# EasyEDApro.net
KiCad netlist of a schematic drawn in EasyEDA Pro
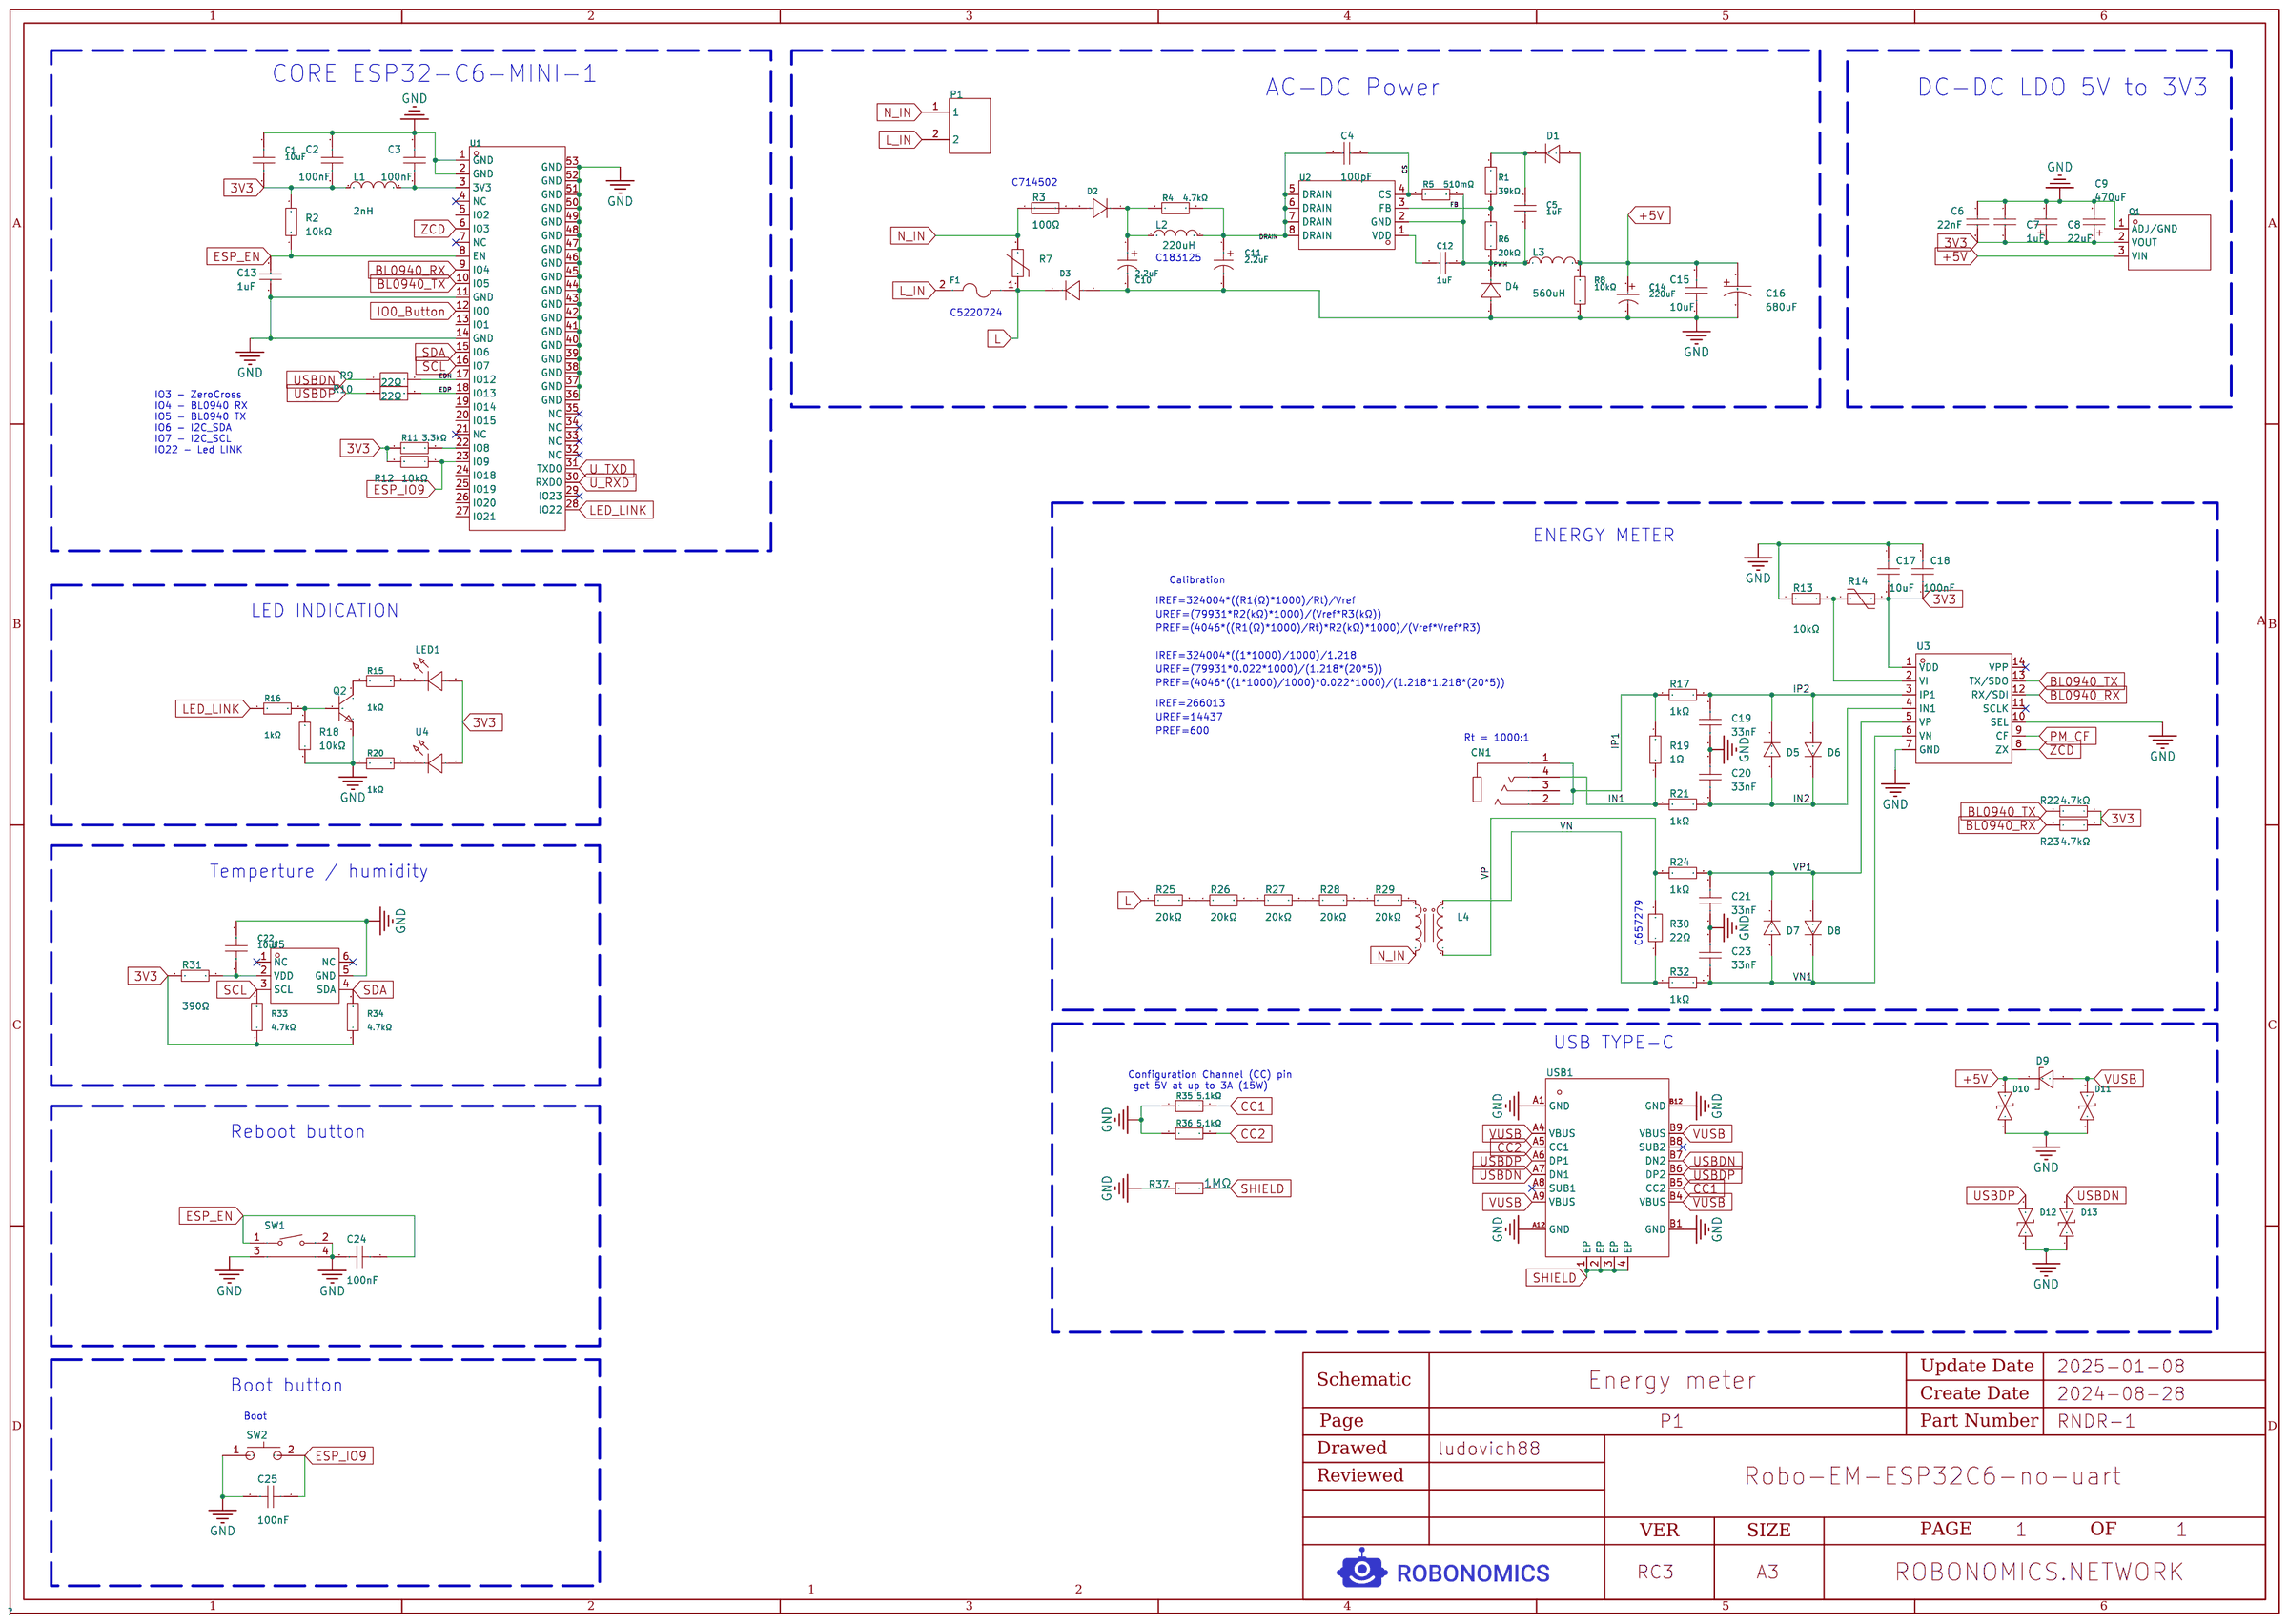
[diagram p0: schematic sheet]

(export (version "E")
  (design (tool "Eeschema 10.0.6"))
  (components
    (comp (ref "C1")
      (value "10uF")
      (footprint "easyedapro:C0603")
      (fields
        (field (name "Manufacturer Part") "GRM188R61E106KA73D")
        (field (name "Manufacturer") "muRata(村田)")
      )
      (libsource (lib "easyedapro") (part "GRM188R61E106KA73D"))
    )
    (comp (ref "C2")
      (value "100nF")
      (fields
        (field (name "Manufacturer Part") "CC0603KRX7R9BB104")
        (field (name "Manufacturer") "YAGEO(国巨)")
      )
      (libsource (lib "easyedapro") (part "0603f104z500"))
    )
    (comp (ref "C3")
      (value "100nF")
      (fields
        (field (name "Manufacturer Part") "CC0603KRX7R9BB104")
        (field (name "Manufacturer") "YAGEO(国巨)")
      )
      (libsource (lib "easyedapro") (part "0603f104z500"))
    )
    (comp (ref "C4")
      (value "100pF")
      (footprint "easyedapro:C1206")
      (fields (field (name "Manufacturer Part") "1206CG101J102NT") (field (name "Manufacturer") "FH(风华)"))
      (libsource (lib "easyedapro") (part "1206CG101J102NT"))
    )
    (comp (ref "C5")
      (value "1uF")
      (footprint "easyedapro:C0805")
      (fields
        (field (name "Manufacturer Part") "CL21B105KBFNNNE")
        (field (name "Manufacturer") "SAMSUNG(三星)")
      )
      (libsource (lib "easyedapro") (part "CL21B105KBFNNNE"))
    )
    (comp (ref "C6")
      (value "22nF")
      (footprint "easyedapro:C0603")
      (description "Capacitance:22nF Tolerance:±10% Tolerance:±10% Voltage Rated:50V Temperature Coefficient:X7R")
      (fields
        (field (name "Manufacturer Part") "CL10B223KB8NNNC")
        (field (name "Manufacturer") "SAMSUNG(三星)")
      )
      (libsource (lib "easyedapro") (part "CL10B223KB8NNNC"))
    )
    (comp (ref "C7")
      (value "1uF")
      (footprint "easyedapro:C0603")
      (description "Capacitance:1uF Tolerance:±10% Tolerance:±10% Voltage Rated:50V Temperature Coefficient:X5R")
      (fields
        (field (name "Manufacturer Part") "CL10A105KB8NNNC")
        (field (name "Manufacturer") "SAMSUNG(三星)")
      )
      (libsource (lib "easyedapro") (part "CL10A105KB8NNNC"))
    )
    (comp (ref "C8")
      (value "22uF")
      (footprint "easyedapro:CASE-A_3216")
      (fields (field (name "Manufacturer Part") "TAJA226K010RNJ") (field (name "Manufacturer") "Kyocera AVX"))
      (libsource (lib "easyedapro") (part "TAJA226K010RNJ"))
    )
    (comp (ref "C9")
      (value "470uF")
      (footprint "easyedapro:CASE-D_7343")
      (fields (field (name "Manufacturer Part") "6TPE470MAZU") (field (name "Manufacturer") "PANASONIC(松下)"))
      (libsource (lib "easyedapro") (part "6TPE470MAZU"))
    )
    (comp (ref "C10")
      (value "2.2uF")
      (footprint "easyedapro:CAP-TH_BD6.3-P2.50-D0.5-FD")
      (fields
        (field (name "Manufacturer Part") "ECH2GM2R2E09OTZO")
        (field (name "Manufacturer") "Yunxing(云星)")
      )
      (libsource (lib "easyedapro") (part "ECH2GM2R2E09OTZO"))
    )
    (comp (ref "C11")
      (value "2.2uF")
      (footprint "easyedapro:CAP-TH_BD6.3-P2.50-D0.5-FD")
      (fields
        (field (name "Manufacturer Part") "ECH2GM2R2E09OTZO")
        (field (name "Manufacturer") "Yunxing(云星)")
      )
      (libsource (lib "easyedapro") (part "ECH2GM2R2E09OTZO"))
    )
    (comp (ref "C12")
      (value "1uF")
      (footprint "easyedapro:C0805")
      (fields
        (field (name "Manufacturer Part") "CL21B105KBFNNNE")
        (field (name "Manufacturer") "SAMSUNG(三星)")
      )
      (libsource (lib "easyedapro") (part "CL21B105KBFNNNE"))
    )
    (comp (ref "C13")
      (value "1uF")
      (footprint "easyedapro:C0603")
      (fields
        (field (name "Manufacturer Part") "CL10A105KO8NNNC")
        (field (name "Manufacturer") "SAMSUNG(三星)")
      )
      (libsource (lib "easyedapro") (part "CL10A105KO8NNNC"))
    )
    (comp (ref "C14")
      (value "220uF")
      (footprint "easyedapro:CAP-TH_BD6.3-P2.50-D1.0-FD")
      (fields
        (field (name "Manufacturer Part") "16YXJ220M6.3X11")
        (field (name "Manufacturer") "rubycon(红宝石)")
      )
      (libsource (lib "easyedapro") (part "16YXJ220M6.3X11"))
    )
    (comp (ref "C15")
      (value "10uF")
      (fields
        (field (name "Manufacturer Part") "CL10A106KP8NNNC")
        (field (name "Manufacturer") "SAMSUNG(三星)")
      )
      (libsource (lib "easyedapro") (part "cl10a106kp8nnnc"))
    )
    (comp (ref "C16")
      (value "680uF")
      (footprint "easyedapro:CAP-SMD_L7.3-W4.3")
      (fields (field (name "Manufacturer Part") "TAJE687K006RNJ") (field (name "Manufacturer") "KyoceraAVX"))
      (libsource (lib "easyedapro") (part "TAJE687K006RNJ"))
    )
    (comp (ref "C17")
      (value "10uF")
      (footprint "easyedapro:C0603")
      (fields
        (field (name "Manufacturer Part") "CL10A106MQ8NNNC")
        (field (name "Manufacturer") "SAMSUNG(三星)")
      )
      (libsource (lib "easyedapro") (part "CL10A106MQ8NNNC"))
    )
    (comp (ref "C18")
      (value "100nF")
      (footprint "easyedapro:C0603")
      (fields (field (name "Manufacturer Part") "0603ZC104KAT2A") (field (name "Manufacturer") "KyoceraAVX"))
      (libsource (lib "easyedapro") (part "0603ZC104KAT2A"))
    )
    (comp (ref "C19")
      (value "33nF")
      (footprint "easyedapro:C0603")
      (fields
        (field (name "Manufacturer Part") "CC0603JRX7R9BB333")
        (field (name "Manufacturer") "YAGEO(国巨)")
      )
      (libsource (lib "easyedapro") (part "CC0603JRX7R9BB333"))
    )
    (comp (ref "C20")
      (value "33nF")
      (footprint "easyedapro:C0603")
      (fields
        (field (name "Manufacturer Part") "CC0603JRX7R9BB333")
        (field (name "Manufacturer") "YAGEO(国巨)")
      )
      (libsource (lib "easyedapro") (part "CC0603JRX7R9BB333"))
    )
    (comp (ref "C21")
      (value "33nF")
      (footprint "easyedapro:C0603")
      (fields
        (field (name "Manufacturer Part") "CC0603JRX7R9BB333")
        (field (name "Manufacturer") "YAGEO(国巨)")
      )
      (libsource (lib "easyedapro") (part "CC0603JRX7R9BB333"))
    )
    (comp (ref "C22")
      (value "10uF")
      (footprint "easyedapro:C0603")
      (fields
        (field (name "Manufacturer Part") "GRM188R61E106KA73D")
        (field (name "Manufacturer") "muRata(村田)")
      )
      (libsource (lib "easyedapro") (part "GRM188R61E106KA73D"))
    )
    (comp (ref "C23")
      (value "33nF")
      (footprint "easyedapro:C0603")
      (fields
        (field (name "Manufacturer Part") "CC0603JRX7R9BB333")
        (field (name "Manufacturer") "YAGEO(国巨)")
      )
      (libsource (lib "easyedapro") (part "CC0603JRX7R9BB333"))
    )
    (comp (ref "C24")
      (value "100nF")
      (footprint "easyedapro:C0603")
      (fields (field (name "Manufacturer Part") "0603ZC104KAT2A") (field (name "Manufacturer") "KyoceraAVX"))
      (libsource (lib "easyedapro") (part "0603ZC104KAT2A"))
    )
    (comp (ref "C25")
      (value "100nF")
      (footprint "easyedapro:C0603")
      (fields
        (field (name "Manufacturer Part") "CC0603KRX7R9BB104")
        (field (name "Manufacturer") "YAGEO(国巨)")
      )
      (libsource (lib "easyedapro") (part "0603ZC104KAT2A"))
    )
    (comp (ref "CN1")
      (value "PJ-320D")
      (footprint "easyedapro:AUDIO-SMD_PJ-320D")
      (fields (field (name "Manufacturer") "SHOU HAN(首韩)"))
      (libsource (lib "easyedapro") (part "PJ-320D"))
    )
    (comp (ref "D1")
      (value "FR107W")
      (footprint "easyedapro:SOD-123F_L2.8-W1.8-LS3.7-RD")
      (fields (field (name "Manufacturer") "SHIKUES(时科)"))
      (libsource (lib "easyedapro") (part "FR107W_C122857"))
    )
    (comp (ref "D2")
      (value "1N4007")
      (footprint "easyedapro:SOD-123FL_L2.8-W1.8-LS3.7-RD")
      (fields (field (name "Manufacturer") "YONGYUTAI(永裕泰)"))
      (libsource (lib "easyedapro") (part "1N4007_C2892681"))
    )
    (comp (ref "D3")
      (value "1N4007")
      (footprint "easyedapro:SOD-123FL_L2.8-W1.8-LS3.7-RD")
      (fields (field (name "Manufacturer") "YONGYUTAI(永裕泰)"))
      (libsource (lib "easyedapro") (part "1N4007_C2892681"))
    )
    (comp (ref "D4")
      (value "E1J")
      (footprint "easyedapro:SOD-123FL_L2.7-W1.8-LS3.7-RD")
      (fields (field (name "Manufacturer") "LGE(鲁光)"))
      (libsource (lib "easyedapro") (part "E1J_C2940141"))
    )
    (comp (ref "D5")
      (value "1N4148WS")
      (footprint "easyedapro:SOD-323_L1.8-W1.3-LS2.5-RD")
      (fields (field (name "Manufacturer") "CJ(江苏长电/长晶)"))
      (libsource (lib "easyedapro") (part "1N4148WS T4"))
    )
    (comp (ref "D6")
      (value "1N4148WS")
      (footprint "easyedapro:SOD-323_L1.8-W1.3-LS2.5-RD")
      (fields (field (name "Manufacturer") "CJ(江苏长电/长晶)"))
      (libsource (lib "easyedapro") (part "1N4148WS T4"))
    )
    (comp (ref "D7")
      (value "1N4148WS")
      (footprint "easyedapro:SOD-323_L1.8-W1.3-LS2.5-RD")
      (fields (field (name "Manufacturer") "CJ(江苏长电/长晶)"))
      (libsource (lib "easyedapro") (part "1N4148WS T4"))
    )
    (comp (ref "D8")
      (value "1N4148WS")
      (footprint "easyedapro:SOD-323_L1.8-W1.3-LS2.5-RD")
      (fields (field (name "Manufacturer") "CJ(江苏长电/长晶)"))
      (libsource (lib "easyedapro") (part "1N4148WS T4"))
    )
    (comp (ref "D9")
      (value "~")
      (footprint "easyedapro:SOD-323_L1.8-W1.3-LS2.5-RD")
      (description "Reverse Voltage (Vr):40V Average Rectified Current (Io):1A Forward Voltage (Vf@If):600mV@1A")
      (fields (field (name "Manufacturer Part") "1N5819WS") (field (name "Manufacturer") "Hottech(合科泰)"))
      (libsource (lib "easyedapro") (part "1N5819WS"))
    )
    (comp (ref "D10")
      (value "LESD5D5.0CT1G-ES")
      (footprint "easyedapro:SOD-523_L1.2-W0.8-LS1.6-BI")
      (fields
        (field (name "Manufacturer Part") "LESD5D5.0CT1G")
        (field (name "Manufacturer") "ElecSuper(静芯微)")
      )
      (libsource (lib "easyedapro") (part "LESD5D5.0CT1G"))
    )
    (comp (ref "D11")
      (value "LESD5D5.0CT1G-ES")
      (footprint "easyedapro:SOD-523_L1.2-W0.8-LS1.6-BI")
      (fields
        (field (name "Manufacturer Part") "LESD5D5.0CT1G")
        (field (name "Manufacturer") "ElecSuper(静芯微)")
      )
      (libsource (lib "easyedapro") (part "LESD5D5.0CT1G"))
    )
    (comp (ref "D12")
      (value "LESD5D5.0CT1G-ES")
      (footprint "easyedapro:SOD-523_L1.2-W0.8-LS1.6-BI")
      (fields
        (field (name "Manufacturer Part") "LESD5D5.0CT1G")
        (field (name "Manufacturer") "ElecSuper(静芯微)")
      )
      (libsource (lib "easyedapro") (part "LESD5D5.0CT1G"))
    )
    (comp (ref "D13")
      (value "LESD5D5.0CT1G-ES")
      (footprint "easyedapro:SOD-523_L1.2-W0.8-LS1.6-BI")
      (fields
        (field (name "Manufacturer Part") "LESD5D5.0CT1G")
        (field (name "Manufacturer") "ElecSuper(静芯微)")
      )
      (libsource (lib "easyedapro") (part "LESD5D5.0CT1G"))
    )
    (comp (ref "F1")
      (value "JFC2410-1200FS")
      (footprint "easyedapro:F2410")
      (fields (field (name "Manufacturer") "JDTfuse(集电通)"))
      (libsource (lib "easyedapro") (part "JFC2410-1200FS"))
    )
    (comp (ref "L1")
      (value "2nH")
      (footprint "easyedapro:L0603")
      (fields
        (field (name "Manufacturer Part") "SDCL1608C2N0STDF")
        (field (name "Manufacturer") "Sunlord(顺络)")
      )
      (libsource (lib "easyedapro") (part "SDCL1608C2N0STDF_C370234"))
    )
    (comp (ref "L2")
      (value "220uH")
      (footprint "easyedapro:IND-TH_BD4.0-P5.00-D0.8")
      (fields (field (name "Manufacturer Part") "LGA0410-221KP13E") (field (name "Manufacturer") "FH(风华)"))
      (libsource (lib "easyedapro") (part "LGA0410-221KP13E"))
    )
    (comp (ref "L3")
      (value "560uH")
      (footprint "easyedapro:IND-SMD_L10.5-W10.5")
      (description "Inductance: Tolerance:±20% Tolerance:±20% Rated Current: DC Resistance (DCR): Type:屏蔽电感")
      (fields
        (field (name "Manufacturer Part") "SCDS105R-561M-N")
        (field (name "Manufacturer") "chilisin(奇力新)")
      )
      (libsource (lib "easyedapro") (part "SCDS105R-561M-N"))
    )
    (comp (ref "L4")
      (value "HPT225A-G")
      (footprint "easyedapro:XFMR-TH_4P-L19.0-10.0-P7.20")
      (fields (field (name "Manufacturer") "HOP(北京霍远)"))
      (libsource (lib "easyedapro") (part "HPT225A-G"))
    )
    (comp (ref "LED1")
      (value "XL-4008UGC")
      (footprint "easyedapro:LED-SMD_L4.0-W1.4-RD_GREEN")
      (fields (field (name "Manufacturer") "XINGLIGHT(成兴光)"))
      (libsource (lib "easyedapro") (part "XL-4008UGC"))
    )
    (comp (ref "P1")
      (value "WJ128V-5.0-2P")
      (footprint "easyedapro:CONN-TH_2P-P5.00_WJ128V-5.0-2P")
      (fields (field (name "Manufacturer") "KANGNEX(康奈克斯电气)"))
      (libsource (lib "easyedapro") (part "WJ128V-5.0-2P"))
    )
    (comp (ref "Q1")
      (value "AMS1117-3.3V")
      (footprint "easyedapro:SOT-89-3_L4.5-W2.5-P1.50-LS4.2-BR")
      (fields (field (name "Manufacturer") "MSKSEMI(美森科)"))
      (libsource (lib "easyedapro") (part "AMS1117-3.3V_C5120796"))
    )
    (comp (ref "Q2")
      (value "SS8050")
      (footprint "easyedapro:SOT-23-3_L2.9-W1.6-P1.90-LS2.8-BR")
      (fields (field (name "Manufacturer") "Hottech(合科泰)"))
      (libsource (lib "easyedapro") (part "SS8050_C181160"))
    )
    (comp (ref "R1")
      (value "39kΩ")
      (footprint "easyedapro:R0805")
      (fields
        (field (name "Manufacturer Part") "0805W8J0393T5E")
        (field (name "Manufacturer") "UNI-ROYAL(厚声)")
      )
      (libsource (lib "easyedapro") (part "HPCR0805F39K0K9"))
    )
    (comp (ref "R2")
      (value "10kΩ")
      (footprint "easyedapro:R0402")
      (fields (field (name "Manufacturer Part") "RC0402FR-0710KL") (field (name "Manufacturer") "YAGEO(国巨)"))
      (libsource (lib "easyedapro") (part "RC0402FR-0710KL"))
    )
    (comp (ref "R3")
      (value "100Ω")
      (footprint "easyedapro:RES-TH_BD3.5-L9.5-P13.50-D0.6")
      (fields (field (name "Manufacturer Part") "RFS01J1000A520NH") (field (name "Manufacturer") "双羽"))
      (libsource (lib "easyedapro") (part "RFS01J1000A520NH"))
    )
    (comp (ref "R4")
      (value "4.7kΩ")
      (footprint "easyedapro:R0603")
      (fields
        (field (name "Manufacturer Part") "0603WAF4701T5E")
        (field (name "Manufacturer") "UNI-ROYAL(厚声)")
      )
      (libsource (lib "easyedapro") (part "0603WAF4701T5E"))
    )
    (comp (ref "R5")
      (value "510mΩ")
      (footprint "easyedapro:R1206")
      (fields (field (name "Manufacturer Part") "RTT06R510FTP") (field (name "Manufacturer") "RALEC(旺诠)"))
      (libsource (lib "easyedapro") (part "RTT06R510FTP"))
    )
    (comp (ref "R6")
      (value "20kΩ")
      (footprint "easyedapro:R0805")
      (fields (field (name "Manufacturer Part") "RTT052002FTP") (field (name "Manufacturer") "RALEC(旺诠)"))
      (libsource (lib "easyedapro") (part "RTT052002FTP"))
    )
    (comp (ref "R7")
      (value "07D471K68RV0149")
      (footprint "easyedapro:RES-SMD_L8.2-W6.3")
      (fields (field (name "Manufacturer") "KNSCHA(科尼盛)"))
      (libsource (lib "easyedapro") (part "07D471K68RV0149"))
    )
    (comp (ref "R8")
      (value "10kΩ")
      (fields
        (field (name "Manufacturer Part") "0805W8F1002T5E")
        (field (name "Manufacturer") "UNI-ROYAL(厚声)")
      )
      (libsource (lib "easyedapro") (part "0805W8J0103T5E"))
    )
    (comp (ref "R9")
      (value "22Ω")
      (footprint "easyedapro:R0402")
      (fields (field (name "Manufacturer Part") "AF0402JR-0722RL") (field (name "Manufacturer") "YAGEO(国巨)"))
      (libsource (lib "easyedapro") (part "AF0402JR-0722RL"))
    )
    (comp (ref "R10")
      (value "22Ω")
      (footprint "easyedapro:R0402")
      (fields (field (name "Manufacturer Part") "AF0402JR-0722RL") (field (name "Manufacturer") "YAGEO(国巨)"))
      (libsource (lib "easyedapro") (part "AF0402JR-0722RL"))
    )
    (comp (ref "R11")
      (value "3.3kΩ")
      (footprint "easyedapro:R0402")
      (fields
        (field (name "Manufacturer Part") "0402WGF3301TCE")
        (field (name "Manufacturer") "UNI-ROYAL(厚声)")
      )
      (libsource (lib "easyedapro") (part "0402WGF3301TCE"))
    )
    (comp (ref "R12")
      (value "10kΩ")
      (footprint "easyedapro:R0402")
      (fields (field (name "Manufacturer Part") "RC0402FR-0710KL") (field (name "Manufacturer") "YAGEO(国巨)"))
      (libsource (lib "easyedapro") (part "RC0402FR-0710KL"))
    )
    (comp (ref "R13")
      (value "10kΩ")
      (footprint "easyedapro:R0402")
      (fields (field (name "Manufacturer Part") "RC0402FR-0710KL") (field (name "Manufacturer") "YAGEO(国巨)"))
      (libsource (lib "easyedapro") (part "RC0402FR-0710KL"))
    )
    (comp (ref "R14")
      (value "CMFA103J3950HANT")
      (footprint "easyedapro:R0603")
      (fields (field (name "Manufacturer") "FH(风华)"))
      (libsource (lib "easyedapro") (part "CMFA103J3950HANT"))
    )
    (comp (ref "R15")
      (value "1kΩ")
      (footprint "easyedapro:R0402")
      (fields
        (field (name "Manufacturer Part") "0402WGF1001TCE")
        (field (name "Manufacturer") "UNI-ROYAL(厚声)")
      )
      (libsource (lib "easyedapro") (part "0402WGF1001TCE"))
    )
    (comp (ref "R16")
      (value "1kΩ")
      (footprint "easyedapro:R0402")
      (fields
        (field (name "Manufacturer Part") "0402WGF1001TCE")
        (field (name "Manufacturer") "UNI-ROYAL(厚声)")
      )
      (libsource (lib "easyedapro") (part "0402WGF1001TCE"))
    )
    (comp (ref "R17")
      (value "1kΩ")
      (fields (field (name "Manufacturer Part") "RT0603BRD071KL") (field (name "Manufacturer") "YAGEO(国巨)"))
      (libsource (lib "easyedapro") (part "ARG03DTC1001"))
    )
    (comp (ref "R18")
      (value "10kΩ")
      (footprint "easyedapro:R0402")
      (fields (field (name "Manufacturer Part") "RC0402FR-0710KL") (field (name "Manufacturer") "YAGEO(国巨)"))
      (libsource (lib "easyedapro") (part "RC0402FR-0710KL"))
    )
    (comp (ref "R19")
      (value "1Ω")
      (footprint "easyedapro:R0603")
      (fields
        (field (name "Manufacturer Part") "0603WAF100KT5E")
        (field (name "Manufacturer") "UNI-ROYAL(厚声)")
      )
      (libsource (lib "easyedapro") (part "0603WAF100KT5E"))
    )
    (comp (ref "R20")
      (value "1kΩ")
      (footprint "easyedapro:R0402")
      (fields
        (field (name "Manufacturer Part") "0402WGF1001TCE")
        (field (name "Manufacturer") "UNI-ROYAL(厚声)")
      )
      (libsource (lib "easyedapro") (part "0402WGF1001TCE"))
    )
    (comp (ref "R21")
      (value "1kΩ")
      (fields (field (name "Manufacturer Part") "RT0603BRD071KL") (field (name "Manufacturer") "YAGEO(国巨)"))
      (libsource (lib "easyedapro") (part "ARG03DTC1001"))
    )
    (comp (ref "R22")
      (value "4.7kΩ")
      (footprint "easyedapro:R0603")
      (fields
        (field (name "Manufacturer Part") "0603WAF4701T5E")
        (field (name "Manufacturer") "UNI-ROYAL(厚声)")
      )
      (libsource (lib "easyedapro") (part "RMC06034.7K5%N"))
    )
    (comp (ref "R23")
      (value "4.7kΩ")
      (footprint "easyedapro:R0603")
      (fields
        (field (name "Manufacturer Part") "0603WAF4701T5E")
        (field (name "Manufacturer") "UNI-ROYAL(厚声)")
      )
      (libsource (lib "easyedapro") (part "RMC06034.7K5%N"))
    )
    (comp (ref "R24")
      (value "1kΩ")
      (fields (field (name "Manufacturer Part") "RT0603BRD071KL") (field (name "Manufacturer") "YAGEO(国巨)"))
      (libsource (lib "easyedapro") (part "ARG03DTC1001"))
    )
    (comp (ref "R25")
      (value "20kΩ")
      (footprint "easyedapro:R0603")
      (fields (field (name "Manufacturer Part") "RMC060320K5%N") (field (name "Manufacturer") "Tyohm(幸亚电阻)"))
      (libsource (lib "easyedapro") (part "RMC060320K5%N"))
    )
    (comp (ref "R26")
      (value "20kΩ")
      (footprint "easyedapro:R0603")
      (fields (field (name "Manufacturer Part") "RMC060320K5%N") (field (name "Manufacturer") "Tyohm(幸亚电阻)"))
      (libsource (lib "easyedapro") (part "RMC060320K5%N"))
    )
    (comp (ref "R27")
      (value "20kΩ")
      (footprint "easyedapro:R0603")
      (fields (field (name "Manufacturer Part") "RMC060320K5%N") (field (name "Manufacturer") "Tyohm(幸亚电阻)"))
      (libsource (lib "easyedapro") (part "RMC060320K5%N"))
    )
    (comp (ref "R28")
      (value "20kΩ")
      (footprint "easyedapro:R0603")
      (fields (field (name "Manufacturer Part") "RMC060320K5%N") (field (name "Manufacturer") "Tyohm(幸亚电阻)"))
      (libsource (lib "easyedapro") (part "RMC060320K5%N"))
    )
    (comp (ref "R29")
      (value "20kΩ")
      (footprint "easyedapro:R0603")
      (fields (field (name "Manufacturer Part") "RMC060320K5%N") (field (name "Manufacturer") "Tyohm(幸亚电阻)"))
      (libsource (lib "easyedapro") (part "RMC060320K5%N"))
    )
    (comp (ref "R30")
      (value "22Ω")
      (footprint "easyedapro:R0603")
      (fields (field (name "Manufacturer Part") "TD03G22R0BT") (field (name "Manufacturer") "FH(风华)"))
      (libsource (lib "easyedapro") (part "TD03G22R0BT"))
    )
    (comp (ref "R31")
      (value "390Ω")
      (footprint "easyedapro:R0402")
      (fields (field (name "Manufacturer Part") "AC0402FR-07390RL") (field (name "Manufacturer") "YAGEO(国巨)"))
      (libsource (lib "easyedapro") (part "AC0402FR-07390RL"))
    )
    (comp (ref "R32")
      (value "1kΩ")
      (fields (field (name "Manufacturer Part") "RT0603BRD071KL") (field (name "Manufacturer") "YAGEO(国巨)"))
      (libsource (lib "easyedapro") (part "ARG03DTC1001"))
    )
    (comp (ref "R33")
      (value "4.7kΩ")
      (footprint "easyedapro:R0402")
      (fields
        (field (name "Manufacturer Part") "0402WGF4701TCE")
        (field (name "Manufacturer") "UNI-ROYAL(厚声)")
      )
      (libsource (lib "easyedapro") (part "0402WGF4701TCE"))
    )
    (comp (ref "R34")
      (value "4.7kΩ")
      (footprint "easyedapro:R0402")
      (fields
        (field (name "Manufacturer Part") "0402WGF4701TCE")
        (field (name "Manufacturer") "UNI-ROYAL(厚声)")
      )
      (libsource (lib "easyedapro") (part "0402WGF4701TCE"))
    )
    (comp (ref "R35")
      (value "5.1kΩ")
      (footprint "easyedapro:R0402")
      (fields
        (field (name "Manufacturer Part") "0402WGF5101TCE")
        (field (name "Manufacturer") "UNI-ROYAL(厚声)")
      )
      (libsource (lib "easyedapro") (part "0402WGF5101TCE"))
    )
    (comp (ref "R36")
      (value "5.1kΩ")
      (footprint "easyedapro:R0402")
      (fields
        (field (name "Manufacturer Part") "0402WGF5101TCE")
        (field (name "Manufacturer") "UNI-ROYAL(厚声)")
      )
      (libsource (lib "easyedapro") (part "0402WGF5101TCE"))
    )
    (comp (ref "R37")
      (value "1MΩ")
      (footprint "easyedapro:R0603")
      (fields
        (field (name "Manufacturer Part") "0603WAF1004T5E")
        (field (name "Manufacturer") "UNI-ROYAL(厚声)")
      )
      (libsource (lib "easyedapro") (part "0603WAF1004T5E"))
    )
    (comp (ref "SW1")
      (value "TS-1010-C-A")
      (footprint "easyedapro:KEY-SMD_TX-1010-X-X")
      (fields (field (name "Manufacturer") "XKBConnectivity(中国星坤)"))
      (libsource (lib "easyedapro") (part "TS-1010-C-A"))
    )
    (comp (ref "SW2")
      (value "~")
      (footprint "easyedapro:SW-SMD_L3.9-W2.9-P4.15-LS5.0")
      (fields
        (field (name "Manufacturer Part") "GT-TC029B-H020-L1N")
        (field (name "Manufacturer") "G-Switch(品赞)")
      )
      (libsource (lib "easyedapro") (part "GT-TC029B-H020-L1N"))
    )
    (comp (ref "U1")
      (value "ESP32-C6-MINI-1-N4")
      (footprint "easyedapro:WIFIM-SMD_61P-L16.6-W13.2-P0.80-ESP32-C6-MINI-1-N4")
      (fields (field (name "Manufacturer") "ESPRESSIF(乐鑫)"))
      (libsource (lib "easyedapro") (part "ESP32-C6-MINI-1-N4"))
    )
    (comp (ref "U2")
      (value "KP15051SPA")
      (footprint "easyedapro:SOP-8_L4.9-W3.8-P1.27-LS6.0-BL")
      (fields (field (name "Manufacturer") "Kiwi Instruments(必易微)"))
      (libsource (lib "easyedapro") (part "KP15051SPA"))
    )
    (comp (ref "U3")
      (value "BL0940")
      (footprint "easyedapro:TSSOP-14_L5.0-W4.4-P0.65-LS6.4-BL")
      (fields (field (name "Manufacturer") "BL(上海贝岭)"))
      (libsource (lib "easyedapro") (part "BL0940"))
    )
    (comp (ref "U4")
      (value "XL-4008SURC")
      (footprint "easyedapro:LED-SMD_L4.0-W1.4-FD_C9900036310")
      (fields (field (name "Manufacturer") "XINGLIGHT(成兴光)"))
      (libsource (lib "easyedapro") (part "XL-4008SURC"))
    )
    (comp (ref "U5")
      (value "AHT20")
      (footprint "easyedapro:SENSOR-SMD_L3.0-W3.0-P1.00-BR")
      (fields (field (name "Manufacturer") "广州奥松"))
      (libsource (lib "easyedapro") (part "AHT20_C2757850"))
    )
    (comp (ref "USB1")
      (value "KH-TYPE-C-16P")
      (footprint "easyedapro:USB-C-SMD_KH-TYPE-C-16P")
      (fields (field (name "Manufacturer") "kinghelm(金航标)"))
      (libsource (lib "easyedapro") (part "KH-TYPE-C-16P"))
    )
  )
  (nets
    (net (code "1") (name "+5V") (class "Default")
      (node (ref "C14") (pin "1") (pinfunction "1_1") (pintype "input"))
      (node (ref "C15") (pin "2") (pinfunction "2_2") (pintype "input"))
      (node (ref "C16") (pin "1") (pinfunction "1_1") (pintype "input"))
      (node (ref "D1") (pin "2") (pinfunction "A_2") (pintype "unspecified"))
      (node (ref "D10") (pin "2") (pinfunction "2_2") (pintype "input"))
      (node (ref "D9") (pin "1") (pinfunction "C_1") (pintype "input"))
      (node (ref "L3") (pin "2") (pinfunction "2_2") (pintype "unspecified"))
      (node (ref "Q1") (pin "3") (pinfunction "VIN_3") (pintype "input"))
      (node (ref "R8") (pin "2") (pinfunction "2_2") (pintype "input"))
    )
    (net (code "2") (name "/CS") (class "Default")
      (node (ref "C4") (pin "1") (pinfunction "1_1") (pintype "input"))
      (node (ref "R5") (pin "1") (pinfunction "1_1") (pintype "input"))
      (node (ref "U2") (pin "4") (pinfunction "CS_4") (pintype "input"))
    )
    (net (code "3") (name "/DRAIN") (class "Default")
      (node (ref "C11") (pin "1") (pinfunction "1_1") (pintype "input"))
      (node (ref "C4") (pin "2") (pinfunction "2_2") (pintype "input"))
      (node (ref "L2") (pin "2") (pinfunction "2_2") (pintype "unspecified"))
      (node (ref "R4") (pin "2") (pinfunction "2_2") (pintype "input"))
      (node (ref "U2") (pin "5") (pinfunction "DRAIN_5") (pintype "input"))
      (node (ref "U2") (pin "6") (pinfunction "DRAIN_6") (pintype "input"))
      (node (ref "U2") (pin "7") (pinfunction "DRAIN_7") (pintype "input"))
      (node (ref "U2") (pin "8") (pinfunction "DRAIN_8") (pintype "input"))
    )
    (net (code "4") (name "/EDN") (class "Default")
      (node (ref "R9") (pin "2") (pinfunction "2_2") (pintype "unspecified"))
      (node (ref "U1") (pin "17") (pinfunction "IO12_17") (pintype "input"))
    )
    (net (code "5") (name "/EDP") (class "Default")
      (node (ref "R10") (pin "2") (pinfunction "2_2") (pintype "unspecified"))
      (node (ref "U1") (pin "18") (pinfunction "IO13_18") (pintype "input"))
    )
    (net (code "6") (name "/FB") (class "Default")
      (node (ref "R1") (pin "1") (pinfunction "1_1") (pintype "input"))
      (node (ref "R6") (pin "2") (pinfunction "2_2") (pintype "input"))
      (node (ref "U2") (pin "3") (pinfunction "FB_3") (pintype "input"))
    )
    (net (code "7") (name "/IN1") (class "Default")
      (node (ref "CN1") (pin "4") (pinfunction "4_4") (pintype "input"))
      (node (ref "R19") (pin "1") (pinfunction "1_1") (pintype "input"))
      (node (ref "R21") (pin "1") (pinfunction "1_1") (pintype "input"))
    )
    (net (code "8") (name "/IN2") (class "Default")
      (node (ref "C20") (pin "1") (pinfunction "1_1") (pintype "input"))
      (node (ref "D5") (pin "2") (pinfunction "A_2") (pintype "input"))
      (node (ref "D6") (pin "1") (pinfunction "K_1") (pintype "input"))
      (node (ref "R21") (pin "2") (pinfunction "2_2") (pintype "input"))
      (node (ref "U3") (pin "4") (pinfunction "IN1_4") (pintype "input"))
    )
    (net (code "9") (name "/IP1") (class "Default")
      (node (ref "CN1") (pin "1") (pinfunction "1_1") (pintype "input"))
      (node (ref "CN1") (pin "2") (pinfunction "2_2") (pintype "input"))
      (node (ref "R17") (pin "1") (pinfunction "1_1") (pintype "input"))
      (node (ref "R19") (pin "2") (pinfunction "2_2") (pintype "input"))
    )
    (net (code "10") (name "/IP2") (class "Default")
      (node (ref "C19") (pin "2") (pinfunction "2_2") (pintype "input"))
      (node (ref "D5") (pin "1") (pinfunction "K_1") (pintype "input"))
      (node (ref "D6") (pin "2") (pinfunction "A_2") (pintype "input"))
      (node (ref "R17") (pin "2") (pinfunction "2_2") (pintype "input"))
      (node (ref "U3") (pin "3") (pinfunction "IP1_3") (pintype "input"))
    )
    (net (code "11") (name "/PWM") (class "Default")
      (node (ref "C12") (pin "1") (pinfunction "1_1") (pintype "input"))
      (node (ref "C5") (pin "1") (pinfunction "1_1") (pintype "input"))
      (node (ref "D4") (pin "1") (pinfunction "K_1") (pintype "unspecified"))
      (node (ref "L3") (pin "1") (pinfunction "1_1") (pintype "unspecified"))
      (node (ref "R5") (pin "2") (pinfunction "2_2") (pintype "input"))
      (node (ref "R6") (pin "1") (pinfunction "1_1") (pintype "input"))
      (node (ref "U2") (pin "2") (pinfunction "GND_2") (pintype "input"))
    )
    (net (code "12") (name "/VN") (class "Default")
      (node (ref "L4") (pin "3") (pinfunction "3_3") (pintype "input"))
      (node (ref "R30") (pin "1") (pinfunction "1_1") (pintype "input"))
      (node (ref "R32") (pin "1") (pinfunction "1_1") (pintype "input"))
    )
    (net (code "13") (name "/VN1") (class "Default")
      (node (ref "C23") (pin "1") (pinfunction "1_1") (pintype "input"))
      (node (ref "D7") (pin "2") (pinfunction "A_2") (pintype "input"))
      (node (ref "D8") (pin "1") (pinfunction "K_1") (pintype "input"))
      (node (ref "R32") (pin "2") (pinfunction "2_2") (pintype "input"))
      (node (ref "U3") (pin "6") (pinfunction "VN_6") (pintype "input"))
    )
    (net (code "14") (name "/VP") (class "Default")
      (node (ref "L4") (pin "4") (pinfunction "4_4") (pintype "input"))
      (node (ref "R24") (pin "1") (pinfunction "1_1") (pintype "input"))
      (node (ref "R30") (pin "2") (pinfunction "2_2") (pintype "input"))
    )
    (net (code "15") (name "/VP1") (class "Default")
      (node (ref "C21") (pin "2") (pinfunction "2_2") (pintype "input"))
      (node (ref "D7") (pin "1") (pinfunction "K_1") (pintype "input"))
      (node (ref "D8") (pin "2") (pinfunction "A_2") (pintype "input"))
      (node (ref "R24") (pin "2") (pinfunction "2_2") (pintype "input"))
      (node (ref "U3") (pin "5") (pinfunction "VP_5") (pintype "input"))
    )
    (net (code "16") (name "3V3") (class "Default")
      (node (ref "C1") (pin "2") (pinfunction "2_2") (pintype "input"))
      (node (ref "C17") (pin "2") (pinfunction "2_2") (pintype "input"))
      (node (ref "C18") (pin "1") (pinfunction "1_1") (pintype "input"))
      (node (ref "C2") (pin "2") (pinfunction "2_2") (pintype "input"))
      (node (ref "C6") (pin "2") (pinfunction "2_2") (pintype "input"))
      (node (ref "C7") (pin "2") (pinfunction "2_2") (pintype "input"))
      (node (ref "C8") (pin "1") (pinfunction "1_1") (pintype "input"))
      (node (ref "C9") (pin "1") (pinfunction "1_1") (pintype "input"))
      (node (ref "L1") (pin "1") (pinfunction "1_1") (pintype "input"))
      (node (ref "LED1") (pin "2") (pinfunction "A_2") (pintype "input"))
      (node (ref "Q1") (pin "2") (pinfunction "VOUT_2") (pintype "input"))
      (node (ref "R11") (pin "1") (pinfunction "1_1") (pintype "input"))
      (node (ref "R12") (pin "2") (pinfunction "2_2") (pintype "input"))
      (node (ref "R14") (pin "2") (pinfunction "2_2") (pintype "unspecified"))
      (node (ref "R2") (pin "2") (pinfunction "2_2") (pintype "input"))
      (node (ref "R22") (pin "1") (pinfunction "1_1") (pintype "input"))
      (node (ref "R23") (pin "1") (pinfunction "1_1") (pintype "input"))
      (node (ref "R31") (pin "1") (pinfunction "1_1") (pintype "unspecified"))
      (node (ref "R33") (pin "1") (pinfunction "1_1") (pintype "input"))
      (node (ref "R34") (pin "1") (pinfunction "1_1") (pintype "input"))
      (node (ref "U3") (pin "1") (pinfunction "VDD_1") (pintype "input"))
      (node (ref "U4") (pin "1") (pinfunction "A_1") (pintype "input"))
    )
    (net (code "17") (name "BL0940_RX") (class "Default")
      (node (ref "R23") (pin "2") (pinfunction "2_2") (pintype "input"))
      (node (ref "U1") (pin "9") (pinfunction "IO4_9") (pintype "input"))
      (node (ref "U3") (pin "12") (pinfunction "RX/SDI_12") (pintype "input"))
    )
    (net (code "18") (name "BL0940_TX") (class "Default")
      (node (ref "R22") (pin "2") (pinfunction "2_2") (pintype "input"))
      (node (ref "U1") (pin "10") (pinfunction "IO5_10") (pintype "input"))
      (node (ref "U3") (pin "13") (pinfunction "TX/SDO_13") (pintype "input"))
    )
    (net (code "19") (name "CC1") (class "Default")
      (node (ref "R35") (pin "2") (pinfunction "2_2") (pintype "input"))
      (node (ref "USB1") (pin "B5") (pinfunction "CC2_B5") (pintype "input"))
    )
    (net (code "20") (name "CC2") (class "Default")
      (node (ref "R36") (pin "2") (pinfunction "2_2") (pintype "input"))
      (node (ref "USB1") (pin "A5") (pinfunction "CC1_A5") (pintype "input"))
    )
    (net (code "21") (name "ESP_EN") (class "Default")
      (node (ref "C13") (pin "1") (pinfunction "1_1") (pintype "input"))
      (node (ref "C24") (pin "1") (pinfunction "1_1") (pintype "input"))
      (node (ref "R2") (pin "1") (pinfunction "1_1") (pintype "input"))
      (node (ref "SW1") (pin "1") (pinfunction "1_1") (pintype "input"))
      (node (ref "U1") (pin "8") (pinfunction "EN_8") (pintype "input"))
    )
    (net (code "22") (name "ESP_IO9") (class "Default")
      (node (ref "C25") (pin "1") (pinfunction "1_1") (pintype "input"))
      (node (ref "R12") (pin "1") (pinfunction "1_1") (pintype "input"))
      (node (ref "SW2") (pin "2") (pinfunction "2_2") (pintype "input"))
      (node (ref "U1") (pin "23") (pinfunction "IO9_23") (pintype "input"))
    )
    (net (code "23") (name "GND") (class "Default")
      (node (ref "C1") (pin "1") (pinfunction "1_1") (pintype "input"))
      (node (ref "C10") (pin "2") (pinfunction "2_2") (pintype "input"))
      (node (ref "C11") (pin "2") (pinfunction "2_2") (pintype "input"))
      (node (ref "C13") (pin "2") (pinfunction "2_2") (pintype "input"))
      (node (ref "C14") (pin "2") (pinfunction "2_2") (pintype "input"))
      (node (ref "C15") (pin "1") (pinfunction "1_1") (pintype "input"))
      (node (ref "C16") (pin "2") (pinfunction "2_2") (pintype "input"))
      (node (ref "C17") (pin "1") (pinfunction "1_1") (pintype "input"))
      (node (ref "C18") (pin "2") (pinfunction "2_2") (pintype "input"))
      (node (ref "C19") (pin "1") (pinfunction "1_1") (pintype "input"))
      (node (ref "C2") (pin "1") (pinfunction "1_1") (pintype "input"))
      (node (ref "C20") (pin "2") (pinfunction "2_2") (pintype "input"))
      (node (ref "C21") (pin "1") (pinfunction "1_1") (pintype "input"))
      (node (ref "C22") (pin "2") (pinfunction "2_2") (pintype "input"))
      (node (ref "C23") (pin "2") (pinfunction "2_2") (pintype "input"))
      (node (ref "C24") (pin "2") (pinfunction "2_2") (pintype "input"))
      (node (ref "C25") (pin "2") (pinfunction "2_2") (pintype "input"))
      (node (ref "C3") (pin "1") (pinfunction "1_1") (pintype "input"))
      (node (ref "C6") (pin "1") (pinfunction "1_1") (pintype "input"))
      (node (ref "C7") (pin "1") (pinfunction "1_1") (pintype "input"))
      (node (ref "C8") (pin "2") (pinfunction "2_2") (pintype "input"))
      (node (ref "C9") (pin "2") (pinfunction "2_2") (pintype "input"))
      (node (ref "D10") (pin "1") (pinfunction "1_1") (pintype "input"))
      (node (ref "D11") (pin "1") (pinfunction "1_1") (pintype "input"))
      (node (ref "D12") (pin "1") (pinfunction "1_1") (pintype "input"))
      (node (ref "D13") (pin "1") (pinfunction "1_1") (pintype "input"))
      (node (ref "D3") (pin "2") (pinfunction "A_2") (pintype "input"))
      (node (ref "D4") (pin "2") (pinfunction "A_2") (pintype "unspecified"))
      (node (ref "Q1") (pin "1") (pinfunction "ADJ/GND_1") (pintype "input"))
      (node (ref "Q2") (pin "2") (pinfunction "E_2") (pintype "input"))
      (node (ref "R13") (pin "1") (pinfunction "1_1") (pintype "input"))
      (node (ref "R18") (pin "1") (pinfunction "1_1") (pintype "input"))
      (node (ref "R20") (pin "1") (pinfunction "1_1") (pintype "input"))
      (node (ref "R35") (pin "1") (pinfunction "1_1") (pintype "input"))
      (node (ref "R36") (pin "1") (pinfunction "1_1") (pintype "input"))
      (node (ref "R37") (pin "1") (pinfunction "1_1") (pintype "input"))
      (node (ref "R8") (pin "1") (pinfunction "1_1") (pintype "input"))
      (node (ref "SW1") (pin "2") (pinfunction "2_2") (pintype "input"))
      (node (ref "SW1") (pin "3") (pinfunction "3_3") (pintype "input"))
      (node (ref "SW1") (pin "4") (pinfunction "4_4") (pintype "input"))
      (node (ref "SW2") (pin "1") (pinfunction "1_1") (pintype "input"))
      (node (ref "U1") (pin "1") (pinfunction "GND_1") (pintype "input"))
      (node (ref "U1") (pin "11") (pinfunction "GND_11") (pintype "input"))
      (node (ref "U1") (pin "14") (pinfunction "GND_14") (pintype "input"))
      (node (ref "U1") (pin "2") (pinfunction "GND_2") (pintype "input"))
      (node (ref "U1") (pin "36") (pinfunction "GND_36") (pintype "input"))
      (node (ref "U1") (pin "37") (pinfunction "GND_37") (pintype "input"))
      (node (ref "U1") (pin "38") (pinfunction "GND_38") (pintype "input"))
      (node (ref "U1") (pin "39") (pinfunction "GND_39") (pintype "input"))
      (node (ref "U1") (pin "40") (pinfunction "GND_40") (pintype "input"))
      (node (ref "U1") (pin "41") (pinfunction "GND_41") (pintype "input"))
      (node (ref "U1") (pin "42") (pinfunction "GND_42") (pintype "input"))
      (node (ref "U1") (pin "43") (pinfunction "GND_43") (pintype "input"))
      (node (ref "U1") (pin "44") (pinfunction "GND_44") (pintype "input"))
      (node (ref "U1") (pin "45") (pinfunction "GND_45") (pintype "input"))
      (node (ref "U1") (pin "46") (pinfunction "GND_46") (pintype "input"))
      (node (ref "U1") (pin "47") (pinfunction "GND_47") (pintype "input"))
      (node (ref "U1") (pin "48") (pinfunction "GND_48") (pintype "input"))
      (node (ref "U1") (pin "49") (pinfunction "GND_49") (pintype "input"))
      (node (ref "U1") (pin "50") (pinfunction "GND_50") (pintype "input"))
      (node (ref "U1") (pin "51") (pinfunction "GND_51") (pintype "input"))
      (node (ref "U1") (pin "52") (pinfunction "GND_52") (pintype "input"))
      (node (ref "U1") (pin "53") (pinfunction "GND_53") (pintype "input"))
      (node (ref "U3") (pin "10") (pinfunction "SEL_10") (pintype "input"))
      (node (ref "U3") (pin "7") (pinfunction "GND_7") (pintype "input"))
      (node (ref "U5") (pin "5") (pinfunction "GND_5") (pintype "unspecified"))
      (node (ref "USB1") (pin "A1") (pinfunction "GND_A1") (pintype "input"))
      (node (ref "USB1") (pin "A12") (pinfunction "GND_A12") (pintype "input"))
      (node (ref "USB1") (pin "B1") (pinfunction "GND_B1") (pintype "input"))
      (node (ref "USB1") (pin "B12") (pinfunction "GND_B12") (pintype "input"))
    )
    (net (code "24") (name "IO0_Button") (class "Default")
      (node (ref "U1") (pin "12") (pinfunction "IO0_12") (pintype "input"))
    )
    (net (code "25") (name "L") (class "Default")
      (node (ref "D3") (pin "1") (pinfunction "K_1") (pintype "input"))
      (node (ref "F1") (pin "1") (pinfunction "1_1") (pintype "input"))
      (node (ref "R25") (pin "1") (pinfunction "1_1") (pintype "input"))
      (node (ref "R7") (pin "1") (pinfunction "1_1") (pintype "unspecified"))
    )
    (net (code "26") (name "LED_LINK") (class "Default")
      (node (ref "R16") (pin "1") (pinfunction "1_1") (pintype "input"))
      (node (ref "U1") (pin "28") (pinfunction "IO22_28") (pintype "input"))
    )
    (net (code "27") (name "L_IN") (class "Default")
      (node (ref "F1") (pin "2") (pinfunction "2_2") (pintype "input"))
      (node (ref "P1") (pin "2") (pinfunction "2_2") (pintype "input"))
    )
    (net (code "28") (name "N_IN") (class "Default")
      (node (ref "L4") (pin "2") (pinfunction "2_2") (pintype "input"))
      (node (ref "P1") (pin "1") (pinfunction "1_1") (pintype "input"))
      (node (ref "R3") (pin "1") (pinfunction "1_1") (pintype "unspecified"))
      (node (ref "R7") (pin "2") (pinfunction "2_2") (pintype "unspecified"))
    )
    (net (code "29") (name "Net-(D1-K)") (class "Default")
      (node (ref "C5") (pin "2") (pinfunction "2_2") (pintype "input"))
      (node (ref "D1") (pin "1") (pinfunction "K_1") (pintype "unspecified"))
      (node (ref "R1") (pin "2") (pinfunction "2_2") (pintype "input"))
    )
    (net (code "30") (name "Net-(D2-A)") (class "Default")
      (node (ref "D2") (pin "2") (pinfunction "A_2") (pintype "input"))
      (node (ref "R3") (pin "2") (pinfunction "2_2") (pintype "unspecified"))
    )
    (net (code "31") (name "Net-(D2-K)") (class "Default")
      (node (ref "C10") (pin "1") (pinfunction "1_1") (pintype "input"))
      (node (ref "D2") (pin "1") (pinfunction "K_1") (pintype "input"))
      (node (ref "L2") (pin "1") (pinfunction "1_1") (pintype "unspecified"))
      (node (ref "R4") (pin "1") (pinfunction "1_1") (pintype "input"))
    )
    (net (code "32") (name "Net-(L4-Pad1)") (class "Default")
      (node (ref "L4") (pin "1") (pinfunction "1_1") (pintype "input"))
      (node (ref "R29") (pin "2") (pinfunction "2_2") (pintype "input"))
    )
    (net (code "33") (name "Net-(LED1-K)") (class "Default")
      (node (ref "LED1") (pin "1") (pinfunction "K_1") (pintype "input"))
      (node (ref "R15") (pin "2") (pinfunction "2_2") (pintype "input"))
    )
    (net (code "34") (name "Net-(Q2-B)") (class "Default")
      (node (ref "Q2") (pin "1") (pinfunction "B_1") (pintype "input"))
      (node (ref "R16") (pin "2") (pinfunction "2_2") (pintype "input"))
      (node (ref "R18") (pin "2") (pinfunction "2_2") (pintype "input"))
    )
    (net (code "35") (name "Net-(Q2-C)") (class "Default")
      (node (ref "Q2") (pin "3") (pinfunction "C_3") (pintype "input"))
      (node (ref "R15") (pin "1") (pinfunction "1_1") (pintype "input"))
    )
    (net (code "36") (name "Net-(R25-Pad2)") (class "Default")
      (node (ref "R25") (pin "2") (pinfunction "2_2") (pintype "input"))
      (node (ref "R26") (pin "1") (pinfunction "1_1") (pintype "input"))
    )
    (net (code "37") (name "Net-(R26-Pad2)") (class "Default")
      (node (ref "R26") (pin "2") (pinfunction "2_2") (pintype "input"))
      (node (ref "R27") (pin "1") (pinfunction "1_1") (pintype "input"))
    )
    (net (code "38") (name "Net-(R27-Pad2)") (class "Default")
      (node (ref "R27") (pin "2") (pinfunction "2_2") (pintype "input"))
      (node (ref "R28") (pin "1") (pinfunction "1_1") (pintype "input"))
    )
    (net (code "39") (name "Net-(R28-Pad2)") (class "Default")
      (node (ref "R28") (pin "2") (pinfunction "2_2") (pintype "input"))
      (node (ref "R29") (pin "1") (pinfunction "1_1") (pintype "input"))
    )
    (net (code "40") (name "Net-(U1-3V3)") (class "Default")
      (node (ref "C3") (pin "2") (pinfunction "2_2") (pintype "input"))
      (node (ref "L1") (pin "2") (pinfunction "2_2") (pintype "input"))
      (node (ref "U1") (pin "3") (pinfunction "3V3_3") (pintype "input"))
    )
    (net (code "41") (name "Net-(U1-IO8)") (class "Default")
      (node (ref "R11") (pin "2") (pinfunction "2_2") (pintype "input"))
      (node (ref "U1") (pin "22") (pinfunction "IO8_22") (pintype "input"))
    )
    (net (code "42") (name "Net-(U2-VDD)") (class "Default")
      (node (ref "C12") (pin "2") (pinfunction "2_2") (pintype "input"))
      (node (ref "U2") (pin "1") (pinfunction "VDD_1") (pintype "input"))
    )
    (net (code "43") (name "Net-(U3-VI)") (class "Default")
      (node (ref "R13") (pin "2") (pinfunction "2_2") (pintype "input"))
      (node (ref "R14") (pin "1") (pinfunction "1_1") (pintype "unspecified"))
      (node (ref "U3") (pin "2") (pinfunction "VI_2") (pintype "input"))
    )
    (net (code "44") (name "Net-(U4-K)") (class "Default")
      (node (ref "R20") (pin "2") (pinfunction "2_2") (pintype "input"))
      (node (ref "U4") (pin "2") (pinfunction "K_2") (pintype "input"))
    )
    (net (code "45") (name "Net-(U5-VDD)") (class "Default")
      (node (ref "C22") (pin "1") (pinfunction "1_1") (pintype "input"))
      (node (ref "R31") (pin "2") (pinfunction "2_2") (pintype "unspecified"))
      (node (ref "U5") (pin "2") (pinfunction "VDD_2") (pintype "unspecified"))
    )
    (net (code "46") (name "PM_CF") (class "Default")
      (node (ref "U3") (pin "9") (pinfunction "CF_9") (pintype "input"))
    )
    (net (code "47") (name "SCL") (class "Default")
      (node (ref "R33") (pin "2") (pinfunction "2_2") (pintype "input"))
      (node (ref "U1") (pin "16") (pinfunction "IO7_16") (pintype "input"))
      (node (ref "U5") (pin "3") (pinfunction "SCL_3") (pintype "unspecified"))
    )
    (net (code "48") (name "SDA") (class "Default")
      (node (ref "R34") (pin "2") (pinfunction "2_2") (pintype "input"))
      (node (ref "U1") (pin "15") (pinfunction "IO6_15") (pintype "input"))
      (node (ref "U5") (pin "4") (pinfunction "SDA_4") (pintype "unspecified"))
    )
    (net (code "49") (name "SHIELD") (class "Default")
      (node (ref "R37") (pin "2") (pinfunction "2_2") (pintype "input"))
      (node (ref "USB1") (pin "1") (pinfunction "EP_1") (pintype "input"))
      (node (ref "USB1") (pin "2") (pinfunction "EP_2") (pintype "input"))
      (node (ref "USB1") (pin "3") (pinfunction "EP_3") (pintype "input"))
      (node (ref "USB1") (pin "4") (pinfunction "EP_4") (pintype "input"))
    )
    (net (code "50") (name "USBDN") (class "Default")
      (node (ref "D13") (pin "2") (pinfunction "2_2") (pintype "input"))
      (node (ref "R9") (pin "1") (pinfunction "1_1") (pintype "unspecified"))
      (node (ref "USB1") (pin "A7") (pinfunction "DN1_A7") (pintype "input"))
      (node (ref "USB1") (pin "B7") (pinfunction "DN2_B7") (pintype "input"))
    )
    (net (code "51") (name "USBDP") (class "Default")
      (node (ref "D12") (pin "2") (pinfunction "2_2") (pintype "input"))
      (node (ref "R10") (pin "1") (pinfunction "1_1") (pintype "unspecified"))
      (node (ref "USB1") (pin "A6") (pinfunction "DP1_A6") (pintype "input"))
      (node (ref "USB1") (pin "B6") (pinfunction "DP2_B6") (pintype "input"))
    )
    (net (code "52") (name "U_RXD") (class "Default")
      (node (ref "U1") (pin "30") (pinfunction "RXD0_30") (pintype "input"))
    )
    (net (code "53") (name "U_TXD") (class "Default")
      (node (ref "U1") (pin "31") (pinfunction "TXD0_31") (pintype "input"))
    )
    (net (code "54") (name "VUSB") (class "Default")
      (node (ref "D11") (pin "2") (pinfunction "2_2") (pintype "input"))
      (node (ref "D9") (pin "2") (pinfunction "A_2") (pintype "input"))
      (node (ref "USB1") (pin "A4") (pinfunction "VBUS_A4") (pintype "input"))
      (node (ref "USB1") (pin "A9") (pinfunction "VBUS_A9") (pintype "input"))
      (node (ref "USB1") (pin "B4") (pinfunction "VBUS_B4") (pintype "input"))
      (node (ref "USB1") (pin "B9") (pinfunction "VBUS_B9") (pintype "input"))
    )
    (net (code "55") (name "ZCD") (class "Default")
      (node (ref "U1") (pin "6") (pinfunction "IO3_6") (pintype "input"))
      (node (ref "U3") (pin "8") (pinfunction "ZX_8") (pintype "input"))
    )
    (net (code "56") (name "unconnected-(CN1-Pad3)") (class "Default")
      (node (ref "CN1") (pin "3") (pinfunction "3_3") (pintype "input"))
    )
    (net (code "57") (name "unconnected-(U1-IO1-Pad13)") (class "Default")
      (node (ref "U1") (pin "13") (pinfunction "IO1_13") (pintype "input"))
    )
    (net (code "58") (name "unconnected-(U1-IO2-Pad5)") (class "Default")
      (node (ref "U1") (pin "5") (pinfunction "IO2_5") (pintype "input"))
    )
    (net (code "59") (name "unconnected-(U1-IO14-Pad19)") (class "Default")
      (node (ref "U1") (pin "19") (pinfunction "IO14_19") (pintype "input"))
    )
    (net (code "60") (name "unconnected-(U1-IO15-Pad20)") (class "Default")
      (node (ref "U1") (pin "20") (pinfunction "IO15_20") (pintype "input"))
    )
    (net (code "61") (name "unconnected-(U1-IO18-Pad24)") (class "Default")
      (node (ref "U1") (pin "24") (pinfunction "IO18_24") (pintype "input"))
    )
    (net (code "62") (name "unconnected-(U1-IO19-Pad25)") (class "Default")
      (node (ref "U1") (pin "25") (pinfunction "IO19_25") (pintype "input"))
    )
    (net (code "63") (name "unconnected-(U1-IO20-Pad26)") (class "Default")
      (node (ref "U1") (pin "26") (pinfunction "IO20_26") (pintype "input"))
    )
    (net (code "64") (name "unconnected-(U1-IO21-Pad27)") (class "Default")
      (node (ref "U1") (pin "27") (pinfunction "IO21_27") (pintype "input"))
    )
    (net (code "65") (name "unconnected-(U1-IO23-Pad29)") (class "Default")
      (node (ref "U1") (pin "29") (pinfunction "IO23_29") (pintype "input+no_connect"))
    )
    (net (code "66") (name "unconnected-(U1-NC-Pad4)") (class "Default")
      (node (ref "U1") (pin "4") (pinfunction "NC_4") (pintype "input+no_connect"))
    )
    (net (code "67") (name "unconnected-(U1-NC-Pad7)") (class "Default")
      (node (ref "U1") (pin "7") (pinfunction "NC_7") (pintype "input+no_connect"))
    )
    (net (code "68") (name "unconnected-(U1-NC-Pad21)") (class "Default")
      (node (ref "U1") (pin "21") (pinfunction "NC_21") (pintype "input+no_connect"))
    )
    (net (code "69") (name "unconnected-(U1-NC-Pad32)") (class "Default")
      (node (ref "U1") (pin "32") (pinfunction "NC_32") (pintype "input+no_connect"))
    )
    (net (code "70") (name "unconnected-(U1-NC-Pad33)") (class "Default")
      (node (ref "U1") (pin "33") (pinfunction "NC_33") (pintype "input+no_connect"))
    )
    (net (code "71") (name "unconnected-(U1-NC-Pad34)") (class "Default")
      (node (ref "U1") (pin "34") (pinfunction "NC_34") (pintype "input+no_connect"))
    )
    (net (code "72") (name "unconnected-(U1-NC-Pad35)") (class "Default")
      (node (ref "U1") (pin "35") (pinfunction "NC_35") (pintype "input+no_connect"))
    )
    (net (code "73") (name "unconnected-(U3-SCLK-Pad11)") (class "Default")
      (node (ref "U3") (pin "11") (pinfunction "SCLK_11") (pintype "input+no_connect"))
    )
    (net (code "74") (name "unconnected-(U3-VPP-Pad14)") (class "Default")
      (node (ref "U3") (pin "14") (pinfunction "VPP_14") (pintype "input+no_connect"))
    )
    (net (code "75") (name "unconnected-(U5-NC-Pad1)") (class "Default")
      (node (ref "U5") (pin "1") (pinfunction "NC_1") (pintype "unspecified+no_connect"))
    )
    (net (code "76") (name "unconnected-(U5-NC-Pad6)") (class "Default")
      (node (ref "U5") (pin "6") (pinfunction "NC_6") (pintype "unspecified+no_connect"))
    )
    (net (code "77") (name "unconnected-(USB1-SUB1-PadA8)") (class "Default")
      (node (ref "USB1") (pin "A8") (pinfunction "SUB1_A8") (pintype "input+no_connect"))
    )
    (net (code "78") (name "unconnected-(USB1-SUB2-PadB8)") (class "Default")
      (node (ref "USB1") (pin "B8") (pinfunction "SUB2_B8") (pintype "input+no_connect"))
    )
  )
)
